# SDRAM.net
KiCad netlist of a schematic drawn in Altium Designer
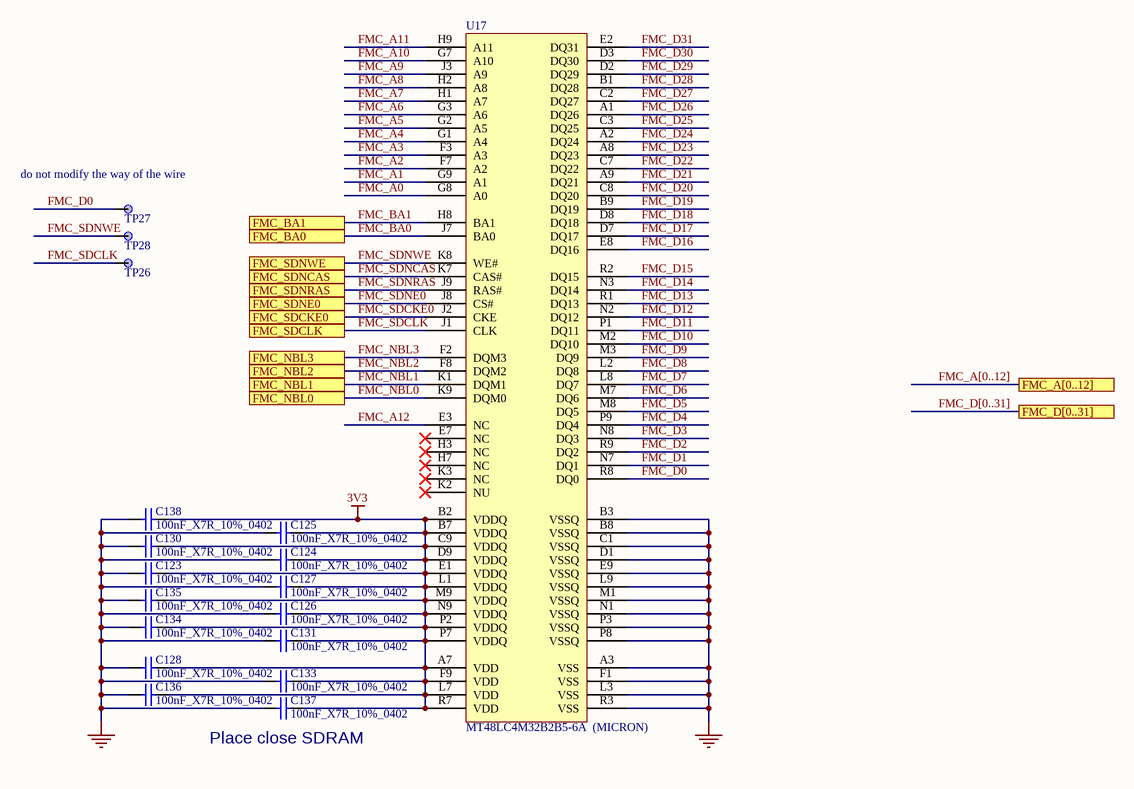
[diagram p0: SDRAM.SchDoc]

(export (version "E")
  (design (tool "Eeschema 10.0.6"))
  (components
    (comp (ref "C123")
      (value "100nF_X7R_10%_0402")
      (footprint "0402C")
      (description "Capacitor,100nF,16V,X7R,10%,0402,YAGEO")
      (libsource (lib "MCD_TOOLS") (part "Cap_100nF_X7R_10%_0402"))
    )
    (comp (ref "C124")
      (value "100nF_X7R_10%_0402")
      (footprint "0402C")
      (description "Capacitor,100nF,16V,X7R,10%,0402,YAGEO")
      (libsource (lib "MCD_TOOLS") (part "Cap_100nF_X7R_10%_0402"))
    )
    (comp (ref "C125")
      (value "100nF_X7R_10%_0402")
      (footprint "0402C")
      (description "Capacitor,100nF,16V,X7R,10%,0402,YAGEO")
      (libsource (lib "MCD_TOOLS") (part "Cap_100nF_X7R_10%_0402"))
    )
    (comp (ref "C126")
      (value "100nF_X7R_10%_0402")
      (footprint "0402C")
      (description "Capacitor,100nF,16V,X7R,10%,0402,YAGEO")
      (libsource (lib "MCD_TOOLS") (part "Cap_100nF_X7R_10%_0402"))
    )
    (comp (ref "C127")
      (value "100nF_X7R_10%_0402")
      (footprint "0402C")
      (description "Capacitor,100nF,16V,X7R,10%,0402,YAGEO")
      (libsource (lib "MCD_TOOLS") (part "Cap_100nF_X7R_10%_0402"))
    )
    (comp (ref "C128")
      (value "100nF_X7R_10%_0402")
      (footprint "0402C")
      (description "Capacitor,100nF,16V,X7R,10%,0402,YAGEO")
      (libsource (lib "MCD_TOOLS") (part "Cap_100nF_X7R_10%_0402"))
    )
    (comp (ref "C130")
      (value "100nF_X7R_10%_0402")
      (footprint "0402C")
      (description "Capacitor,100nF,16V,X7R,10%,0402,YAGEO")
      (libsource (lib "MCD_TOOLS") (part "Cap_100nF_X7R_10%_0402"))
    )
    (comp (ref "C131")
      (value "100nF_X7R_10%_0402")
      (footprint "0402C")
      (description "Capacitor,100nF,16V,X7R,10%,0402,YAGEO")
      (libsource (lib "MCD_TOOLS") (part "Cap_100nF_X7R_10%_0402"))
    )
    (comp (ref "C133")
      (value "100nF_X7R_10%_0402")
      (footprint "0402C")
      (description "Capacitor,100nF,16V,X7R,10%,0402,YAGEO")
      (libsource (lib "MCD_TOOLS") (part "Cap_100nF_X7R_10%_0402"))
    )
    (comp (ref "C134")
      (value "100nF_X7R_10%_0402")
      (footprint "0402C")
      (description "Capacitor,100nF,16V,X7R,10%,0402,YAGEO")
      (libsource (lib "MCD_TOOLS") (part "Cap_100nF_X7R_10%_0402"))
    )
    (comp (ref "C135")
      (value "100nF_X7R_10%_0402")
      (footprint "0402C")
      (description "Capacitor,100nF,16V,X7R,10%,0402,YAGEO")
      (libsource (lib "MCD_TOOLS") (part "Cap_100nF_X7R_10%_0402"))
    )
    (comp (ref "C136")
      (value "100nF_X7R_10%_0402")
      (footprint "0402C")
      (description "Capacitor,100nF,16V,X7R,10%,0402,YAGEO")
      (libsource (lib "MCD_TOOLS") (part "Cap_100nF_X7R_10%_0402"))
    )
    (comp (ref "C137")
      (value "100nF_X7R_10%_0402")
      (footprint "0402C")
      (description "Capacitor,100nF,16V,X7R,10%,0402,YAGEO")
      (libsource (lib "MCD_TOOLS") (part "Cap_100nF_X7R_10%_0402"))
    )
    (comp (ref "C138")
      (value "100nF_X7R_10%_0402")
      (footprint "0402C")
      (description "Capacitor,100nF,16V,X7R,10%,0402,YAGEO")
      (libsource (lib "MCD_TOOLS") (part "Cap_100nF_X7R_10%_0402"))
    )
    (comp (ref "TP26")
      (value "TP")
      (footprint "TP_C40")
      (description "Test Point")
      (libsource (lib "MCD_TOOLS_CONNECTOR") (part "TP"))
    )
    (comp (ref "TP27")
      (value "TP")
      (footprint "TP_C40")
      (description "Test Point")
      (libsource (lib "MCD_TOOLS_CONNECTOR") (part "TP"))
    )
    (comp (ref "TP28")
      (value "TP")
      (footprint "TP_C40")
      (description "Test Point")
      (libsource (lib "MCD_TOOLS_CONNECTOR") (part "TP"))
    )
    (comp (ref "U17")
      (value "MT48LC4M32B2B5-6A  (MICRON)")
      (footprint "FBGA90_0R8_8X13")
      (description "SDRAM 128MBIT (4M x 32) 166MHZ 90-VFBGA (8x13)")
      (libsource (lib "MCD_TOOLS") (part "MT48LC4M32B2B5-6A"))
    )
  )
  (nets
    (net (code "1") (name "/FMC_A0") (class "Default")
      (node (ref "U17") (pin "G8") (pinfunction "A0_G8") (pintype "passive"))
    )
    (net (code "2") (name "/FMC_A1") (class "Default")
      (node (ref "U17") (pin "G9") (pinfunction "A1_G9") (pintype "passive"))
    )
    (net (code "3") (name "/FMC_A2") (class "Default")
      (node (ref "U17") (pin "F7") (pinfunction "A2_F7") (pintype "passive"))
    )
    (net (code "4") (name "/FMC_A3") (class "Default")
      (node (ref "U17") (pin "F3") (pinfunction "A3_F3") (pintype "passive"))
    )
    (net (code "5") (name "/FMC_A4") (class "Default")
      (node (ref "U17") (pin "G1") (pinfunction "A4_G1") (pintype "passive"))
    )
    (net (code "6") (name "/FMC_A5") (class "Default")
      (node (ref "U17") (pin "G2") (pinfunction "A5_G2") (pintype "passive"))
    )
    (net (code "7") (name "/FMC_A6") (class "Default")
      (node (ref "U17") (pin "G3") (pinfunction "A6_G3") (pintype "passive"))
    )
    (net (code "8") (name "/FMC_A7") (class "Default")
      (node (ref "U17") (pin "H1") (pinfunction "A7_H1") (pintype "passive"))
    )
    (net (code "9") (name "/FMC_A8") (class "Default")
      (node (ref "U17") (pin "H2") (pinfunction "A8_H2") (pintype "passive"))
    )
    (net (code "10") (name "/FMC_A9") (class "Default")
      (node (ref "U17") (pin "J3") (pinfunction "A9_J3") (pintype "passive"))
    )
    (net (code "11") (name "/FMC_A10") (class "Default")
      (node (ref "U17") (pin "G7") (pinfunction "A10_G7") (pintype "passive"))
    )
    (net (code "12") (name "/FMC_A11") (class "Default")
      (node (ref "U17") (pin "H9") (pinfunction "A11_H9") (pintype "passive"))
    )
    (net (code "13") (name "/FMC_A12") (class "Default")
      (node (ref "U17") (pin "E3") (pinfunction "NC_E3") (pintype "passive"))
    )
    (net (code "15") (name "/FMC_BA0") (class "Default")
      (node (ref "U17") (pin "J7") (pinfunction "BA0_J7") (pintype "passive"))
    )
    (net (code "16") (name "/FMC_BA1") (class "Default")
      (node (ref "U17") (pin "H8") (pinfunction "BA1_H8") (pintype "passive"))
    )
    (net (code "17") (name "/FMC_D0") (class "Default")
      (node (ref "TP27") (pin "1") (pinfunction "1_1") (pintype "passive"))
      (node (ref "U17") (pin "R8") (pinfunction "DQ0_R8") (pintype "passive"))
    )
    (net (code "18") (name "/FMC_D1") (class "Default")
      (node (ref "U17") (pin "N7") (pinfunction "DQ1_N7") (pintype "passive"))
    )
    (net (code "19") (name "/FMC_D2") (class "Default")
      (node (ref "U17") (pin "R9") (pinfunction "DQ2_R9") (pintype "passive"))
    )
    (net (code "20") (name "/FMC_D3") (class "Default")
      (node (ref "U17") (pin "N8") (pinfunction "DQ3_N8") (pintype "passive"))
    )
    (net (code "21") (name "/FMC_D4") (class "Default")
      (node (ref "U17") (pin "P9") (pinfunction "DQ4_P9") (pintype "passive"))
    )
    (net (code "22") (name "/FMC_D5") (class "Default")
      (node (ref "U17") (pin "M8") (pinfunction "DQ5_M8") (pintype "passive"))
    )
    (net (code "23") (name "/FMC_D6") (class "Default")
      (node (ref "U17") (pin "M7") (pinfunction "DQ6_M7") (pintype "passive"))
    )
    (net (code "24") (name "/FMC_D7") (class "Default")
      (node (ref "U17") (pin "L8") (pinfunction "DQ7_L8") (pintype "passive"))
    )
    (net (code "25") (name "/FMC_D8") (class "Default")
      (node (ref "U17") (pin "L2") (pinfunction "DQ8_L2") (pintype "passive"))
    )
    (net (code "26") (name "/FMC_D9") (class "Default")
      (node (ref "U17") (pin "M3") (pinfunction "DQ9_M3") (pintype "passive"))
    )
    (net (code "27") (name "/FMC_D10") (class "Default")
      (node (ref "U17") (pin "M2") (pinfunction "DQ10_M2") (pintype "passive"))
    )
    (net (code "28") (name "/FMC_D11") (class "Default")
      (node (ref "U17") (pin "P1") (pinfunction "DQ11_P1") (pintype "passive"))
    )
    (net (code "29") (name "/FMC_D12") (class "Default")
      (node (ref "U17") (pin "N2") (pinfunction "DQ12_N2") (pintype "passive"))
    )
    (net (code "30") (name "/FMC_D13") (class "Default")
      (node (ref "U17") (pin "R1") (pinfunction "DQ13_R1") (pintype "passive"))
    )
    (net (code "31") (name "/FMC_D14") (class "Default")
      (node (ref "U17") (pin "N3") (pinfunction "DQ14_N3") (pintype "passive"))
    )
    (net (code "32") (name "/FMC_D15") (class "Default")
      (node (ref "U17") (pin "R2") (pinfunction "DQ15_R2") (pintype "passive"))
    )
    (net (code "33") (name "/FMC_D16") (class "Default")
      (node (ref "U17") (pin "E8") (pinfunction "DQ16_E8") (pintype "passive"))
    )
    (net (code "34") (name "/FMC_D17") (class "Default")
      (node (ref "U17") (pin "D7") (pinfunction "DQ17_D7") (pintype "passive"))
    )
    (net (code "35") (name "/FMC_D18") (class "Default")
      (node (ref "U17") (pin "D8") (pinfunction "DQ18_D8") (pintype "passive"))
    )
    (net (code "36") (name "/FMC_D19") (class "Default")
      (node (ref "U17") (pin "B9") (pinfunction "DQ19_B9") (pintype "passive"))
    )
    (net (code "37") (name "/FMC_D20") (class "Default")
      (node (ref "U17") (pin "C8") (pinfunction "DQ20_C8") (pintype "passive"))
    )
    (net (code "38") (name "/FMC_D21") (class "Default")
      (node (ref "U17") (pin "A9") (pinfunction "DQ21_A9") (pintype "passive"))
    )
    (net (code "39") (name "/FMC_D22") (class "Default")
      (node (ref "U17") (pin "C7") (pinfunction "DQ22_C7") (pintype "passive"))
    )
    (net (code "40") (name "/FMC_D23") (class "Default")
      (node (ref "U17") (pin "A8") (pinfunction "DQ23_A8") (pintype "passive"))
    )
    (net (code "41") (name "/FMC_D24") (class "Default")
      (node (ref "U17") (pin "A2") (pinfunction "DQ24_A2") (pintype "passive"))
    )
    (net (code "42") (name "/FMC_D25") (class "Default")
      (node (ref "U17") (pin "C3") (pinfunction "DQ25_C3") (pintype "passive"))
    )
    (net (code "43") (name "/FMC_D26") (class "Default")
      (node (ref "U17") (pin "A1") (pinfunction "DQ26_A1") (pintype "passive"))
    )
    (net (code "44") (name "/FMC_D27") (class "Default")
      (node (ref "U17") (pin "C2") (pinfunction "DQ27_C2") (pintype "passive"))
    )
    (net (code "45") (name "/FMC_D28") (class "Default")
      (node (ref "U17") (pin "B1") (pinfunction "DQ28_B1") (pintype "passive"))
    )
    (net (code "46") (name "/FMC_D29") (class "Default")
      (node (ref "U17") (pin "D2") (pinfunction "DQ29_D2") (pintype "passive"))
    )
    (net (code "47") (name "/FMC_D30") (class "Default")
      (node (ref "U17") (pin "D3") (pinfunction "DQ30_D3") (pintype "passive"))
    )
    (net (code "48") (name "/FMC_D31") (class "Default")
      (node (ref "U17") (pin "E2") (pinfunction "DQ31_E2") (pintype "passive"))
    )
    (net (code "50") (name "/FMC_NBL0") (class "Default")
      (node (ref "U17") (pin "K9") (pinfunction "DQM0_K9") (pintype "passive"))
    )
    (net (code "51") (name "/FMC_NBL1") (class "Default")
      (node (ref "U17") (pin "K1") (pinfunction "DQM1_K1") (pintype "passive"))
    )
    (net (code "52") (name "/FMC_NBL2") (class "Default")
      (node (ref "U17") (pin "F8") (pinfunction "DQM2_F8") (pintype "passive"))
    )
    (net (code "53") (name "/FMC_NBL3") (class "Default")
      (node (ref "U17") (pin "F2") (pinfunction "DQM3_F2") (pintype "passive"))
    )
    (net (code "54") (name "/FMC_SDCKE0") (class "Default")
      (node (ref "U17") (pin "J2") (pinfunction "CKE_J2") (pintype "passive"))
    )
    (net (code "55") (name "/FMC_SDCLK") (class "Default")
      (node (ref "TP26") (pin "1") (pinfunction "1_1") (pintype "passive"))
      (node (ref "U17") (pin "J1") (pinfunction "CLK_J1") (pintype "passive"))
    )
    (net (code "56") (name "/FMC_SDNCAS") (class "Default")
      (node (ref "U17") (pin "K7") (pinfunction "CAS#_K7") (pintype "passive"))
    )
    (net (code "57") (name "/FMC_SDNE0") (class "Default")
      (node (ref "U17") (pin "J8") (pinfunction "CS#_J8") (pintype "passive"))
    )
    (net (code "58") (name "/FMC_SDNRAS") (class "Default")
      (node (ref "U17") (pin "J9") (pinfunction "RAS#_J9") (pintype "passive"))
    )
    (net (code "59") (name "/FMC_SDNWE") (class "Default")
      (node (ref "TP28") (pin "1") (pinfunction "1_1") (pintype "passive"))
      (node (ref "U17") (pin "K8") (pinfunction "WE#_K8") (pintype "passive"))
    )
    (net (code "60") (name "3V3") (class "Default")
      (node (ref "C123") (pin "2") (pinfunction "2_2") (pintype "passive"))
      (node (ref "C124") (pin "2") (pinfunction "2_2") (pintype "passive"))
      (node (ref "C125") (pin "2") (pinfunction "2_2") (pintype "passive"))
      (node (ref "C126") (pin "2") (pinfunction "2_2") (pintype "passive"))
      (node (ref "C127") (pin "2") (pinfunction "2_2") (pintype "passive"))
      (node (ref "C128") (pin "2") (pinfunction "2_2") (pintype "passive"))
      (node (ref "C130") (pin "2") (pinfunction "2_2") (pintype "passive"))
      (node (ref "C131") (pin "2") (pinfunction "2_2") (pintype "passive"))
      (node (ref "C133") (pin "2") (pinfunction "2_2") (pintype "passive"))
      (node (ref "C134") (pin "2") (pinfunction "2_2") (pintype "passive"))
      (node (ref "C135") (pin "2") (pinfunction "2_2") (pintype "passive"))
      (node (ref "C136") (pin "2") (pinfunction "2_2") (pintype "passive"))
      (node (ref "C137") (pin "2") (pinfunction "2_2") (pintype "passive"))
      (node (ref "C138") (pin "2") (pinfunction "2_2") (pintype "passive"))
      (node (ref "U17") (pin "A7") (pinfunction "VDD_A7") (pintype "passive"))
      (node (ref "U17") (pin "B2") (pinfunction "VDDQ_B2") (pintype "passive"))
      (node (ref "U17") (pin "B7") (pinfunction "VDDQ_B7") (pintype "passive"))
      (node (ref "U17") (pin "C9") (pinfunction "VDDQ_C9") (pintype "passive"))
      (node (ref "U17") (pin "D9") (pinfunction "VDDQ_D9") (pintype "passive"))
      (node (ref "U17") (pin "E1") (pinfunction "VDDQ_E1") (pintype "passive"))
      (node (ref "U17") (pin "F9") (pinfunction "VDD_F9") (pintype "passive"))
      (node (ref "U17") (pin "L1") (pinfunction "VDDQ_L1") (pintype "passive"))
      (node (ref "U17") (pin "L7") (pinfunction "VDD_L7") (pintype "passive"))
      (node (ref "U17") (pin "M9") (pinfunction "VDDQ_M9") (pintype "passive"))
      (node (ref "U17") (pin "N9") (pinfunction "VDDQ_N9") (pintype "passive"))
      (node (ref "U17") (pin "P2") (pinfunction "VDDQ_P2") (pintype "passive"))
      (node (ref "U17") (pin "P7") (pinfunction "VDDQ_P7") (pintype "passive"))
      (node (ref "U17") (pin "R7") (pinfunction "VDD_R7") (pintype "passive"))
    )
    (net (code "61") (name "GND") (class "Default")
      (node (ref "C123") (pin "1") (pinfunction "1_1") (pintype "passive"))
      (node (ref "C124") (pin "1") (pinfunction "1_1") (pintype "passive"))
      (node (ref "C125") (pin "1") (pinfunction "1_1") (pintype "passive"))
      (node (ref "C126") (pin "1") (pinfunction "1_1") (pintype "passive"))
      (node (ref "C127") (pin "1") (pinfunction "1_1") (pintype "passive"))
      (node (ref "C128") (pin "1") (pinfunction "1_1") (pintype "passive"))
      (node (ref "C130") (pin "1") (pinfunction "1_1") (pintype "passive"))
      (node (ref "C131") (pin "1") (pinfunction "1_1") (pintype "passive"))
      (node (ref "C133") (pin "1") (pinfunction "1_1") (pintype "passive"))
      (node (ref "C134") (pin "1") (pinfunction "1_1") (pintype "passive"))
      (node (ref "C135") (pin "1") (pinfunction "1_1") (pintype "passive"))
      (node (ref "C136") (pin "1") (pinfunction "1_1") (pintype "passive"))
      (node (ref "C137") (pin "1") (pinfunction "1_1") (pintype "passive"))
      (node (ref "C138") (pin "1") (pinfunction "1_1") (pintype "passive"))
      (node (ref "U17") (pin "A3") (pinfunction "VSS_A3") (pintype "passive"))
      (node (ref "U17") (pin "B3") (pinfunction "VSSQ_B3") (pintype "passive"))
      (node (ref "U17") (pin "B8") (pinfunction "VSSQ_B8") (pintype "passive"))
      (node (ref "U17") (pin "C1") (pinfunction "VSSQ_C1") (pintype "passive"))
      (node (ref "U17") (pin "D1") (pinfunction "VSSQ_D1") (pintype "passive"))
      (node (ref "U17") (pin "E9") (pinfunction "VSSQ_E9") (pintype "passive"))
      (node (ref "U17") (pin "F1") (pinfunction "VSS_F1") (pintype "passive"))
      (node (ref "U17") (pin "L3") (pinfunction "VSS_L3") (pintype "passive"))
      (node (ref "U17") (pin "L9") (pinfunction "VSSQ_L9") (pintype "passive"))
      (node (ref "U17") (pin "M1") (pinfunction "VSSQ_M1") (pintype "passive"))
      (node (ref "U17") (pin "N1") (pinfunction "VSSQ_N1") (pintype "passive"))
      (node (ref "U17") (pin "P3") (pinfunction "VSSQ_P3") (pintype "passive"))
      (node (ref "U17") (pin "P8") (pinfunction "VSSQ_P8") (pintype "passive"))
      (node (ref "U17") (pin "R3") (pinfunction "VSS_R3") (pintype "passive"))
    )
    (net (code "62") (name "unconnected-(U17-NC-PadE7)") (class "Default")
      (node (ref "U17") (pin "E7") (pinfunction "NC_E7") (pintype "passive+no_connect"))
    )
    (net (code "63") (name "unconnected-(U17-NC-PadH3)") (class "Default")
      (node (ref "U17") (pin "H3") (pinfunction "NC_H3") (pintype "passive+no_connect"))
    )
    (net (code "64") (name "unconnected-(U17-NC-PadH7)") (class "Default")
      (node (ref "U17") (pin "H7") (pinfunction "NC_H7") (pintype "passive+no_connect"))
    )
    (net (code "65") (name "unconnected-(U17-NC-PadK3)") (class "Default")
      (node (ref "U17") (pin "K3") (pinfunction "NC_K3") (pintype "passive+no_connect"))
    )
    (net (code "66") (name "unconnected-(U17-NU-PadK2)") (class "Default")
      (node (ref "U17") (pin "K2") (pinfunction "NU_K2") (pintype "passive+no_connect"))
    )
  )
)
